# transceiver.net
KiCad netlist of a schematic drawn in EAGLE
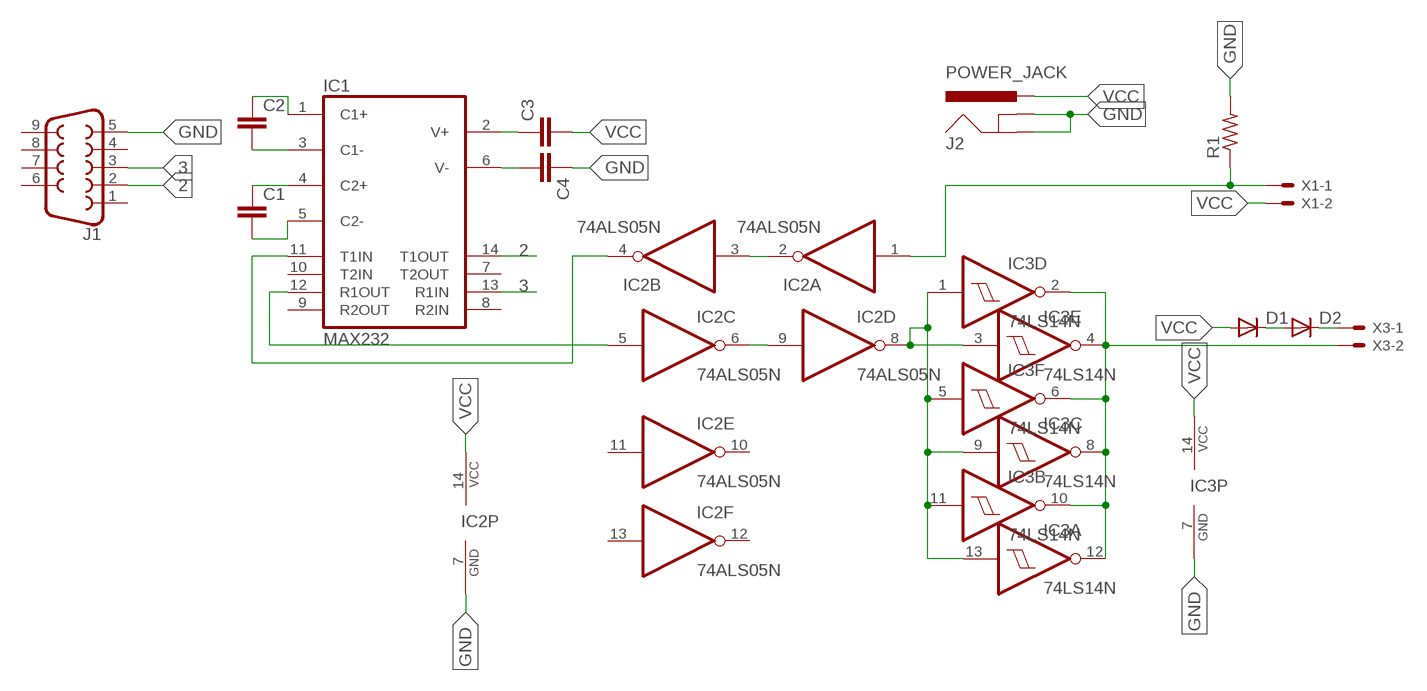
[diagram p0: schematic, sheet 1]

(export (version "E")
  (design (tool "Eeschema 10.0.6"))
  (components
    (comp (ref "C1")
      (value "C2,5-3")
      (footprint "eagle-import:C2.5-3")
      (libsource (lib "eagle-import") (part "C2,5-3"))
    )
    (comp (ref "C2")
      (value "C2,5-3")
      (footprint "eagle-import:C2.5-3")
      (libsource (lib "eagle-import") (part "C2,5-3"))
    )
    (comp (ref "C3")
      (value "C2,5-3")
      (footprint "eagle-import:C2.5-3")
      (libsource (lib "eagle-import") (part "C2,5-3"))
    )
    (comp (ref "C4")
      (value "C2,5-3")
      (footprint "eagle-import:C2.5-3")
      (libsource (lib "eagle-import") (part "C2,5-3"))
    )
    (comp (ref "D1")
      (value "1N4004")
      (footprint "eagle-import:DO41-10")
      (libsource (lib "eagle-import") (part "1N4004"))
    )
    (comp (ref "D2")
      (value "1N4004")
      (footprint "eagle-import:DO41-10")
      (libsource (lib "eagle-import") (part "1N4004"))
    )
    (comp (ref "IC1")
      (value "MAX232")
      (footprint "eagle-import:DIL16")
      (fields (field (name "MF") "MAXIM") (field (name "MPN") "MAX232ACPE+"))
      (libsource (lib "eagle-import") (part "MAX232"))
    )
    (comp (ref "IC2")
      (value "74ALS05N")
      (footprint "eagle-import:DIL14")
      (libsource (lib "eagle-import") (part "7405NALS"))
    )
    (comp (ref "IC3")
      (value "74LS14N")
      (footprint "eagle-import:DIL14")
      (libsource (lib "eagle-import") (part "7414NLS"))
    )
    (comp (ref "J1")
      (value "DB9FEMALE")
      (footprint "eagle-import:DB9")
      (libsource (lib "eagle-import") (part "DB9FEMALE"))
    )
    (comp (ref "J2")
      (value "POWER_JACK")
      (footprint "eagle-import:POWER_JACK_PTH")
      (libsource (lib "eagle-import") (part "POWER_JACK"))
    )
    (comp (ref "R1")
      (value "R-US_0207/12")
      (footprint "eagle-import:0207_12")
      (libsource (lib "eagle-import") (part "R-US_0207/12"))
    )
    (comp (ref "X1")
      (value "JST-XH-02-PIN-LONG-PAD")
      (footprint "eagle-import:JST-XH-02-PACKAGE-LONG-PAD")
      (libsource (lib "eagle-import") (part "JST-XH-02-PIN-LONG-PAD"))
    )
    (comp (ref "X3")
      (value "JST-XH-02-PIN-LONG-PAD")
      (footprint "eagle-import:JST-XH-02-PACKAGE-LONG-PAD")
      (libsource (lib "eagle-import") (part "JST-XH-02-PIN-LONG-PAD"))
    )
  )
  (nets
    (net (code "1") (name "2") (class "Default")
      (node (ref "IC1") (pin "14") (pinfunction "T1OUT_14") (pintype "output"))
      (node (ref "J1") (pin "2") (pinfunction "2_2") (pintype "passive"))
    )
    (net (code "2") (name "3") (class "Default")
      (node (ref "IC1") (pin "13") (pinfunction "R1IN_13") (pintype "input"))
      (node (ref "J1") (pin "3") (pinfunction "3_3") (pintype "passive"))
    )
    (net (code "3") (name "GND") (class "Default")
      (node (ref "C4") (pin "1") (pinfunction "1_1") (pintype "passive"))
      (node (ref "IC2") (pin "7") (pinfunction "GND_7") (pintype "power_in"))
      (node (ref "IC3") (pin "7") (pinfunction "GND_7") (pintype "power_in"))
      (node (ref "J1") (pin "5") (pinfunction "5_5") (pintype "passive"))
      (node (ref "J2") (pin "GND") (pinfunction "GND_GND") (pintype "bidirectional"))
      (node (ref "J2") (pin "GNDBREAK") (pinfunction "GNDBREAK_GNDBREAK") (pintype "bidirectional"))
      (node (ref "R1") (pin "2") (pinfunction "2_2") (pintype "passive"))
    )
    (net (code "4") (name "Net-(D1-PadC)") (class "Default")
      (node (ref "D1") (pin "C") (pinfunction "C_C") (pintype "passive"))
      (node (ref "D2") (pin "A") (pinfunction "A_A") (pintype "passive"))
    )
    (net (code "5") (name "Net-(IC1A-C1+)") (class "Default")
      (node (ref "C2") (pin "1") (pinfunction "1_1") (pintype "passive"))
      (node (ref "IC1") (pin "1") (pinfunction "C1+_1") (pintype "bidirectional"))
    )
    (net (code "6") (name "Net-(IC1A-C1-)") (class "Default")
      (node (ref "C2") (pin "2") (pinfunction "2_2") (pintype "passive"))
      (node (ref "IC1") (pin "3") (pinfunction "C1-_3") (pintype "bidirectional"))
    )
    (net (code "7") (name "Net-(IC1A-C2+)") (class "Default")
      (node (ref "C1") (pin "1") (pinfunction "1_1") (pintype "passive"))
      (node (ref "IC1") (pin "4") (pinfunction "C2+_4") (pintype "bidirectional"))
    )
    (net (code "8") (name "Net-(IC1A-C2-)") (class "Default")
      (node (ref "C1") (pin "2") (pinfunction "2_2") (pintype "passive"))
      (node (ref "IC1") (pin "5") (pinfunction "C2-_5") (pintype "bidirectional"))
    )
    (net (code "9") (name "Net-(IC1A-R1OUT)") (class "Default")
      (node (ref "IC1") (pin "12") (pinfunction "R1OUT_12") (pintype "output"))
      (node (ref "IC2") (pin "5") (pinfunction "I_5") (pintype "input"))
    )
    (net (code "10") (name "Net-(IC1A-T1IN)") (class "Default")
      (node (ref "IC1") (pin "11") (pinfunction "T1IN_11") (pintype "input"))
      (node (ref "IC2") (pin "4") (pinfunction "O_4") (pintype "open_collector"))
    )
    (net (code "11") (name "Net-(IC1A-V+)") (class "Default")
      (node (ref "C3") (pin "1") (pinfunction "1_1") (pintype "passive"))
      (node (ref "IC1") (pin "2") (pinfunction "V+_2") (pintype "bidirectional"))
    )
    (net (code "12") (name "Net-(IC1A-V-)") (class "Default")
      (node (ref "C4") (pin "2") (pinfunction "2_2") (pintype "passive"))
      (node (ref "IC1") (pin "6") (pinfunction "V-_6") (pintype "bidirectional"))
    )
    (net (code "13") (name "Net-(IC2A-I)") (class "Default")
      (node (ref "IC2") (pin "1") (pinfunction "I_1") (pintype "input"))
      (node (ref "R1") (pin "1") (pinfunction "1_1") (pintype "passive"))
      (node (ref "X1") (pin "1") (pinfunction "S_1") (pintype "passive"))
    )
    (net (code "14") (name "Net-(IC2A-O)") (class "Default")
      (node (ref "IC2") (pin "2") (pinfunction "O_2") (pintype "open_collector"))
      (node (ref "IC2") (pin "3") (pinfunction "I_3") (pintype "input"))
    )
    (net (code "15") (name "Net-(IC2C-O)") (class "Default")
      (node (ref "IC2") (pin "6") (pinfunction "O_6") (pintype "open_collector"))
      (node (ref "IC2") (pin "9") (pinfunction "I_9") (pintype "input"))
    )
    (net (code "16") (name "Net-(IC2D-O)") (class "Default")
      (node (ref "IC2") (pin "8") (pinfunction "O_8") (pintype "open_collector"))
      (node (ref "IC3") (pin "1") (pinfunction "I_1") (pintype "input"))
      (node (ref "IC3") (pin "11") (pinfunction "I_11") (pintype "input"))
      (node (ref "IC3") (pin "13") (pinfunction "I_13") (pintype "input"))
      (node (ref "IC3") (pin "3") (pinfunction "I_3") (pintype "input"))
      (node (ref "IC3") (pin "5") (pinfunction "I_5") (pintype "input"))
      (node (ref "IC3") (pin "9") (pinfunction "I_9") (pintype "input"))
    )
    (net (code "17") (name "Net-(IC3A-O)") (class "Default")
      (node (ref "IC3") (pin "10") (pinfunction "O_10") (pintype "output"))
      (node (ref "IC3") (pin "12") (pinfunction "O_12") (pintype "output"))
      (node (ref "IC3") (pin "2") (pinfunction "O_2") (pintype "output"))
      (node (ref "IC3") (pin "4") (pinfunction "O_4") (pintype "output"))
      (node (ref "IC3") (pin "6") (pinfunction "O_6") (pintype "output"))
      (node (ref "IC3") (pin "8") (pinfunction "O_8") (pintype "output"))
      (node (ref "X3") (pin "2") (pinfunction "S_2") (pintype "passive"))
    )
    (net (code "18") (name "Net-(X3A-S)") (class "Default")
      (node (ref "D2") (pin "C") (pinfunction "C_C") (pintype "passive"))
      (node (ref "X3") (pin "1") (pinfunction "S_1") (pintype "passive"))
    )
    (net (code "19") (name "VCC") (class "Default")
      (node (ref "C3") (pin "2") (pinfunction "2_2") (pintype "passive"))
      (node (ref "D1") (pin "A") (pinfunction "A_A") (pintype "passive"))
      (node (ref "IC2") (pin "14") (pinfunction "VCC_14") (pintype "power_in"))
      (node (ref "IC3") (pin "14") (pinfunction "VCC_14") (pintype "power_in"))
      (node (ref "J2") (pin "PWR") (pinfunction "PWR_PWR") (pintype "bidirectional"))
      (node (ref "X1") (pin "2") (pinfunction "S_2") (pintype "passive"))
    )
    (net (code "20") (name "unconnected-(IC1A-R2IN-Pad8)") (class "Default")
      (node (ref "IC1") (pin "8") (pinfunction "R2IN_8") (pintype "input"))
    )
    (net (code "21") (name "unconnected-(IC1A-R2OUT-Pad9)") (class "Default")
      (node (ref "IC1") (pin "9") (pinfunction "R2OUT_9") (pintype "output"))
    )
    (net (code "22") (name "unconnected-(IC1A-T2IN-Pad10)") (class "Default")
      (node (ref "IC1") (pin "10") (pinfunction "T2IN_10") (pintype "input"))
    )
    (net (code "23") (name "unconnected-(IC1A-T2OUT-Pad7)") (class "Default")
      (node (ref "IC1") (pin "7") (pinfunction "T2OUT_7") (pintype "output"))
    )
    (net (code "24") (name "unconnected-(IC2E-I-Pad11)") (class "Default")
      (node (ref "IC2") (pin "11") (pinfunction "I_11") (pintype "input"))
    )
    (net (code "25") (name "unconnected-(IC2E-O-Pad10)") (class "Default")
      (node (ref "IC2") (pin "10") (pinfunction "O_10") (pintype "open_collector"))
    )
    (net (code "26") (name "unconnected-(IC2F-I-Pad13)") (class "Default")
      (node (ref "IC2") (pin "13") (pinfunction "I_13") (pintype "input"))
    )
    (net (code "27") (name "unconnected-(IC2F-O-Pad12)") (class "Default")
      (node (ref "IC2") (pin "12") (pinfunction "O_12") (pintype "open_collector"))
    )
    (net (code "28") (name "unconnected-(J1-Pad1)") (class "Default")
      (node (ref "J1") (pin "1") (pinfunction "1_1") (pintype "passive"))
    )
    (net (code "29") (name "unconnected-(J1-Pad4)") (class "Default")
      (node (ref "J1") (pin "4") (pinfunction "4_4") (pintype "passive"))
    )
    (net (code "30") (name "unconnected-(J1-Pad6)") (class "Default")
      (node (ref "J1") (pin "6") (pinfunction "6_6") (pintype "passive"))
    )
    (net (code "31") (name "unconnected-(J1-Pad7)") (class "Default")
      (node (ref "J1") (pin "7") (pinfunction "7_7") (pintype "passive"))
    )
    (net (code "32") (name "unconnected-(J1-Pad8)") (class "Default")
      (node (ref "J1") (pin "8") (pinfunction "8_8") (pintype "passive"))
    )
    (net (code "33") (name "unconnected-(J1-Pad9)") (class "Default")
      (node (ref "J1") (pin "9") (pinfunction "9_9") (pintype "passive"))
    )
  )
)
